# MotorDriver_Basic.net
KiCad netlist of a schematic drawn in EAGLE
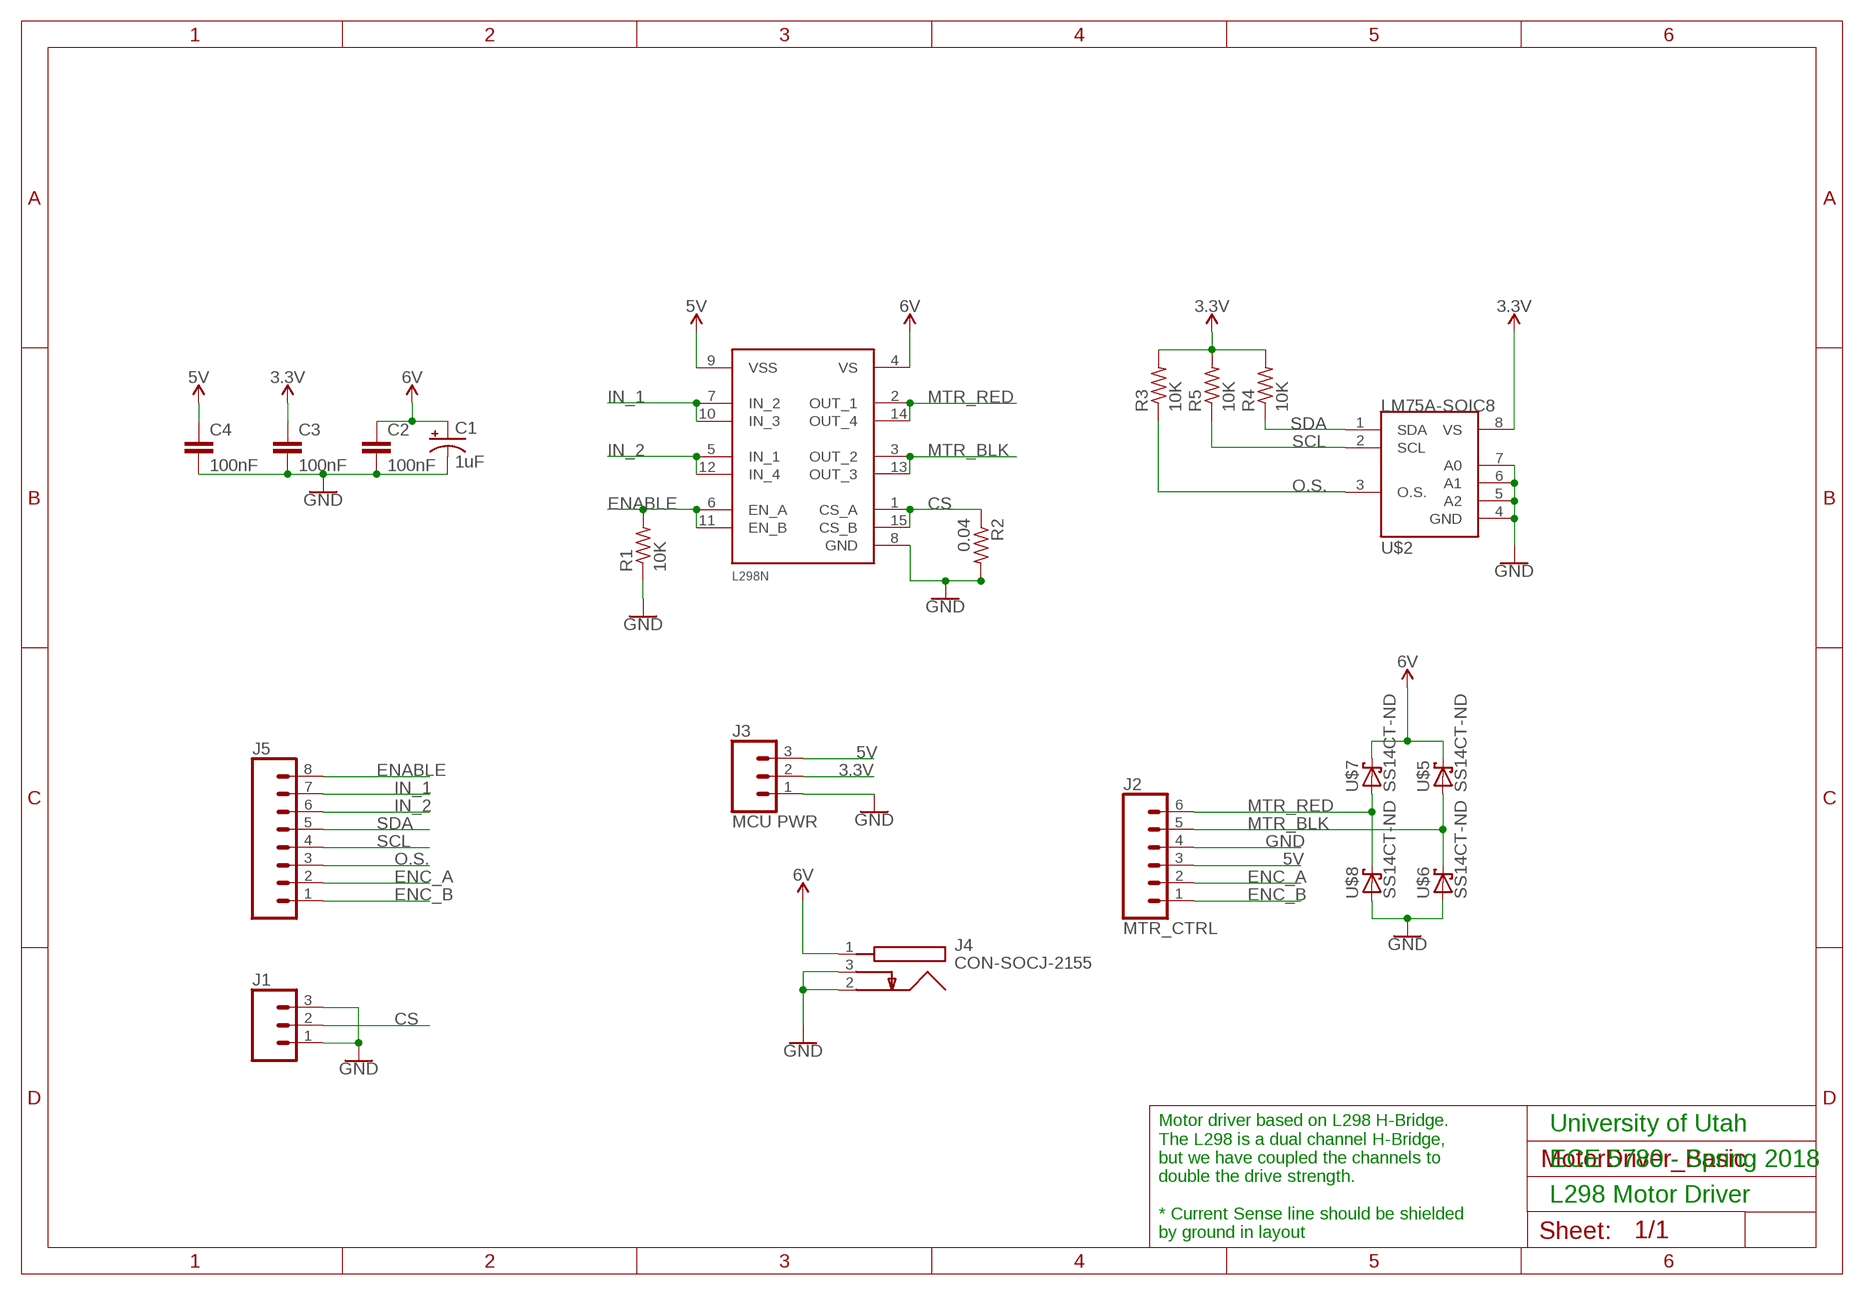
[diagram p0: schematic, sheet 1]

(export (version "E")
  (design (tool "Eeschema 10.0.6"))
  (components
    (comp (ref "C1")
      (value "1uF")
      (footprint "eagle-import:E2,5-6")
      (libsource (lib "eagle-import") (part "CPOL-USE2.5-6"))
    )
    (comp (ref "C2")
      (value "100nF")
      (footprint "eagle-import:C1206")
      (libsource (lib "eagle-import") (part "C-EUC1206"))
    )
    (comp (ref "C3")
      (value "100nF")
      (footprint "eagle-import:C1206")
      (libsource (lib "eagle-import") (part "C-EUC1206"))
    )
    (comp (ref "C4")
      (value "100nF")
      (footprint "eagle-import:C1206")
      (libsource (lib "eagle-import") (part "C-EUC1206"))
    )
    (comp (ref "J1")
      (value "CONN_03")
      (footprint "eagle-import:1X03")
      (libsource (lib "eagle-import") (part "CONN_03"))
    )
    (comp (ref "J2")
      (value "MTR_CTRL")
      (footprint "eagle-import:1X06")
      (libsource (lib "eagle-import") (part "CONN_06SILK_FEMALE_PTH"))
    )
    (comp (ref "J3")
      (value "MCU PWR")
      (footprint "eagle-import:1X03")
      (libsource (lib "eagle-import") (part "CONN_03"))
    )
    (comp (ref "J4")
      (value "CON-SOCJ-2155")
      (footprint "eagle-import:CONSOCJ2155")
      (fields (field (name "MOUSER_PART_NUMBER") "992-CON-SOCJ-2155"))
      (libsource (lib "eagle-import") (part "CON-SOCJ-2155"))
    )
    (comp (ref "J5")
      (value "CONN_08\"")
      (footprint "eagle-import:1X08")
      (libsource (lib "eagle-import") (part "CONN_08{dblquote}"))
    )
    (comp (ref "L298N")
      (value "L298N-MULTIWATT15")
      (footprint "eagle-import:L298N-MULTIWATT15")
      (libsource (lib "eagle-import") (part "L298N-MULTIWATT15"))
    )
    (comp (ref "R1")
      (value "10K")
      (footprint "eagle-import:M1206")
      (libsource (lib "eagle-import") (part "R-US_M1206"))
    )
    (comp (ref "R2")
      (value "0.04")
      (footprint "eagle-import:M1206")
      (libsource (lib "eagle-import") (part "R-US_M1206"))
    )
    (comp (ref "R3")
      (value "10K")
      (footprint "eagle-import:M1206")
      (libsource (lib "eagle-import") (part "R-US_M1206"))
    )
    (comp (ref "R4")
      (value "10K")
      (footprint "eagle-import:M1206")
      (libsource (lib "eagle-import") (part "R-US_M1206"))
    )
    (comp (ref "R5")
      (value "10K")
      (footprint "eagle-import:M1206")
      (libsource (lib "eagle-import") (part "R-US_M1206"))
    )
    (comp (ref "U$2")
      (value "LM75A-SOIC8")
      (footprint "eagle-import:SOIC-8")
      (libsource (lib "eagle-import") (part "LM75A-SOIC8"))
    )
    (comp (ref "U$5")
      (value "SS14CT-ND")
      (footprint "eagle-import:SOD106A-W")
      (libsource (lib "eagle-import") (part "SS14CT-ND"))
    )
    (comp (ref "U$6")
      (value "SS14CT-ND")
      (footprint "eagle-import:SOD106A-W")
      (libsource (lib "eagle-import") (part "SS14CT-ND"))
    )
    (comp (ref "U$7")
      (value "SS14CT-ND")
      (footprint "eagle-import:SOD106A-W")
      (libsource (lib "eagle-import") (part "SS14CT-ND"))
    )
    (comp (ref "U$8")
      (value "SS14CT-ND")
      (footprint "eagle-import:SOD106A-W")
      (libsource (lib "eagle-import") (part "SS14CT-ND"))
    )
  )
  (nets
    (net (code "1") (name "/CS") (class "Default")
      (node (ref "J1") (pin "2") (pinfunction "2_2") (pintype "passive"))
      (node (ref "L298N") (pin "1") (pinfunction "CS_A_1") (pintype "bidirectional"))
      (node (ref "L298N") (pin "15") (pinfunction "CS_B_15") (pintype "bidirectional"))
      (node (ref "R2") (pin "1") (pinfunction "1_1") (pintype "passive"))
    )
    (net (code "2") (name "/ENABLE") (class "Default")
      (node (ref "J5") (pin "8") (pinfunction "8_8") (pintype "passive"))
      (node (ref "L298N") (pin "11") (pinfunction "EN_B_11") (pintype "bidirectional"))
      (node (ref "L298N") (pin "6") (pinfunction "EN_A_6") (pintype "bidirectional"))
      (node (ref "R1") (pin "2") (pinfunction "2_2") (pintype "passive"))
    )
    (net (code "3") (name "/ENC_A") (class "Default")
      (node (ref "J2") (pin "2") (pinfunction "2_2") (pintype "passive"))
      (node (ref "J5") (pin "2") (pinfunction "2_2") (pintype "passive"))
    )
    (net (code "4") (name "/ENC_B") (class "Default")
      (node (ref "J2") (pin "1") (pinfunction "1_1") (pintype "passive"))
      (node (ref "J5") (pin "1") (pinfunction "1_1") (pintype "passive"))
    )
    (net (code "5") (name "/IN_1") (class "Default")
      (node (ref "J5") (pin "7") (pinfunction "7_7") (pintype "passive"))
      (node (ref "L298N") (pin "10") (pinfunction "IN_3_10") (pintype "bidirectional"))
      (node (ref "L298N") (pin "7") (pinfunction "IN_2_7") (pintype "bidirectional"))
    )
    (net (code "6") (name "/IN_2") (class "Default")
      (node (ref "J5") (pin "6") (pinfunction "6_6") (pintype "passive"))
      (node (ref "L298N") (pin "12") (pinfunction "IN_4_12") (pintype "bidirectional"))
      (node (ref "L298N") (pin "5") (pinfunction "IN_1_5") (pintype "bidirectional"))
    )
    (net (code "7") (name "/MTR_BLK") (class "Default")
      (node (ref "J2") (pin "5") (pinfunction "5_5") (pintype "passive"))
      (node (ref "L298N") (pin "13") (pinfunction "OUT_3_13") (pintype "bidirectional"))
      (node (ref "L298N") (pin "3") (pinfunction "OUT_2_3") (pintype "bidirectional"))
      (node (ref "U$5") (pin "A") (pinfunction "A_A") (pintype "passive"))
      (node (ref "U$6") (pin "C") (pinfunction "C_C") (pintype "passive"))
    )
    (net (code "8") (name "/MTR_RED") (class "Default")
      (node (ref "J2") (pin "6") (pinfunction "6_6") (pintype "passive"))
      (node (ref "L298N") (pin "14") (pinfunction "OUT_4_14") (pintype "bidirectional"))
      (node (ref "L298N") (pin "2") (pinfunction "OUT_1_2") (pintype "bidirectional"))
      (node (ref "U$7") (pin "A") (pinfunction "A_A") (pintype "passive"))
      (node (ref "U$8") (pin "C") (pinfunction "C_C") (pintype "passive"))
    )
    (net (code "9") (name "/O.S.") (class "Default")
      (node (ref "J5") (pin "3") (pinfunction "3_3") (pintype "passive"))
      (node (ref "R3") (pin "1") (pinfunction "1_1") (pintype "passive"))
      (node (ref "U$2") (pin "3") (pinfunction "O.S._3") (pintype "bidirectional"))
    )
    (net (code "10") (name "/SCL") (class "Default")
      (node (ref "J5") (pin "4") (pinfunction "4_4") (pintype "passive"))
      (node (ref "R5") (pin "1") (pinfunction "1_1") (pintype "passive"))
      (node (ref "U$2") (pin "2") (pinfunction "SCL_2") (pintype "bidirectional"))
    )
    (net (code "11") (name "/SDA") (class "Default")
      (node (ref "J5") (pin "5") (pinfunction "5_5") (pintype "passive"))
      (node (ref "R4") (pin "1") (pinfunction "1_1") (pintype "passive"))
      (node (ref "U$2") (pin "1") (pinfunction "SDA_1") (pintype "bidirectional"))
    )
    (net (code "12") (name "3.3V") (class "Default")
      (node (ref "C3") (pin "1") (pinfunction "1_1") (pintype "passive"))
      (node (ref "J3") (pin "2") (pinfunction "2_2") (pintype "passive"))
      (node (ref "R3") (pin "2") (pinfunction "2_2") (pintype "passive"))
      (node (ref "R4") (pin "2") (pinfunction "2_2") (pintype "passive"))
      (node (ref "R5") (pin "2") (pinfunction "2_2") (pintype "passive"))
      (node (ref "U$2") (pin "8") (pinfunction "VS_8") (pintype "bidirectional"))
    )
    (net (code "13") (name "5V") (class "Default")
      (node (ref "C4") (pin "1") (pinfunction "1_1") (pintype "passive"))
      (node (ref "J2") (pin "3") (pinfunction "3_3") (pintype "passive"))
      (node (ref "J3") (pin "3") (pinfunction "3_3") (pintype "passive"))
      (node (ref "L298N") (pin "9") (pinfunction "VSS_9") (pintype "bidirectional"))
    )
    (net (code "14") (name "6V") (class "Default")
      (node (ref "C1") (pin "+") (pinfunction "+_+") (pintype "passive"))
      (node (ref "C2") (pin "1") (pinfunction "1_1") (pintype "passive"))
      (node (ref "J4") (pin "1") (pinfunction "1_1") (pintype "bidirectional"))
      (node (ref "L298N") (pin "4") (pinfunction "VS_4") (pintype "bidirectional"))
      (node (ref "U$5") (pin "C") (pinfunction "C_C") (pintype "passive"))
      (node (ref "U$7") (pin "C") (pinfunction "C_C") (pintype "passive"))
    )
    (net (code "15") (name "GND") (class "Default")
      (node (ref "C1") (pin "-") (pinfunction "-_-") (pintype "passive"))
      (node (ref "C2") (pin "2") (pinfunction "2_2") (pintype "passive"))
      (node (ref "C3") (pin "2") (pinfunction "2_2") (pintype "passive"))
      (node (ref "C4") (pin "2") (pinfunction "2_2") (pintype "passive"))
      (node (ref "J1") (pin "1") (pinfunction "1_1") (pintype "passive"))
      (node (ref "J1") (pin "3") (pinfunction "3_3") (pintype "passive"))
      (node (ref "J2") (pin "4") (pinfunction "4_4") (pintype "passive"))
      (node (ref "J3") (pin "1") (pinfunction "1_1") (pintype "passive"))
      (node (ref "J4") (pin "2") (pinfunction "2_2") (pintype "bidirectional"))
      (node (ref "J4") (pin "3") (pinfunction "3_3") (pintype "bidirectional"))
      (node (ref "L298N") (pin "8") (pinfunction "GND_8") (pintype "bidirectional"))
      (node (ref "R1") (pin "1") (pinfunction "1_1") (pintype "passive"))
      (node (ref "R2") (pin "2") (pinfunction "2_2") (pintype "passive"))
      (node (ref "U$2") (pin "4") (pinfunction "GND_4") (pintype "bidirectional"))
      (node (ref "U$2") (pin "5") (pinfunction "A2_5") (pintype "bidirectional"))
      (node (ref "U$2") (pin "6") (pinfunction "A1_6") (pintype "bidirectional"))
      (node (ref "U$2") (pin "7") (pinfunction "A0_7") (pintype "bidirectional"))
      (node (ref "U$6") (pin "A") (pinfunction "A_A") (pintype "passive"))
      (node (ref "U$8") (pin "A") (pinfunction "A_A") (pintype "passive"))
    )
  )
)
